# Sheet1.net
KiCad netlist of a schematic drawn in Altium Designer
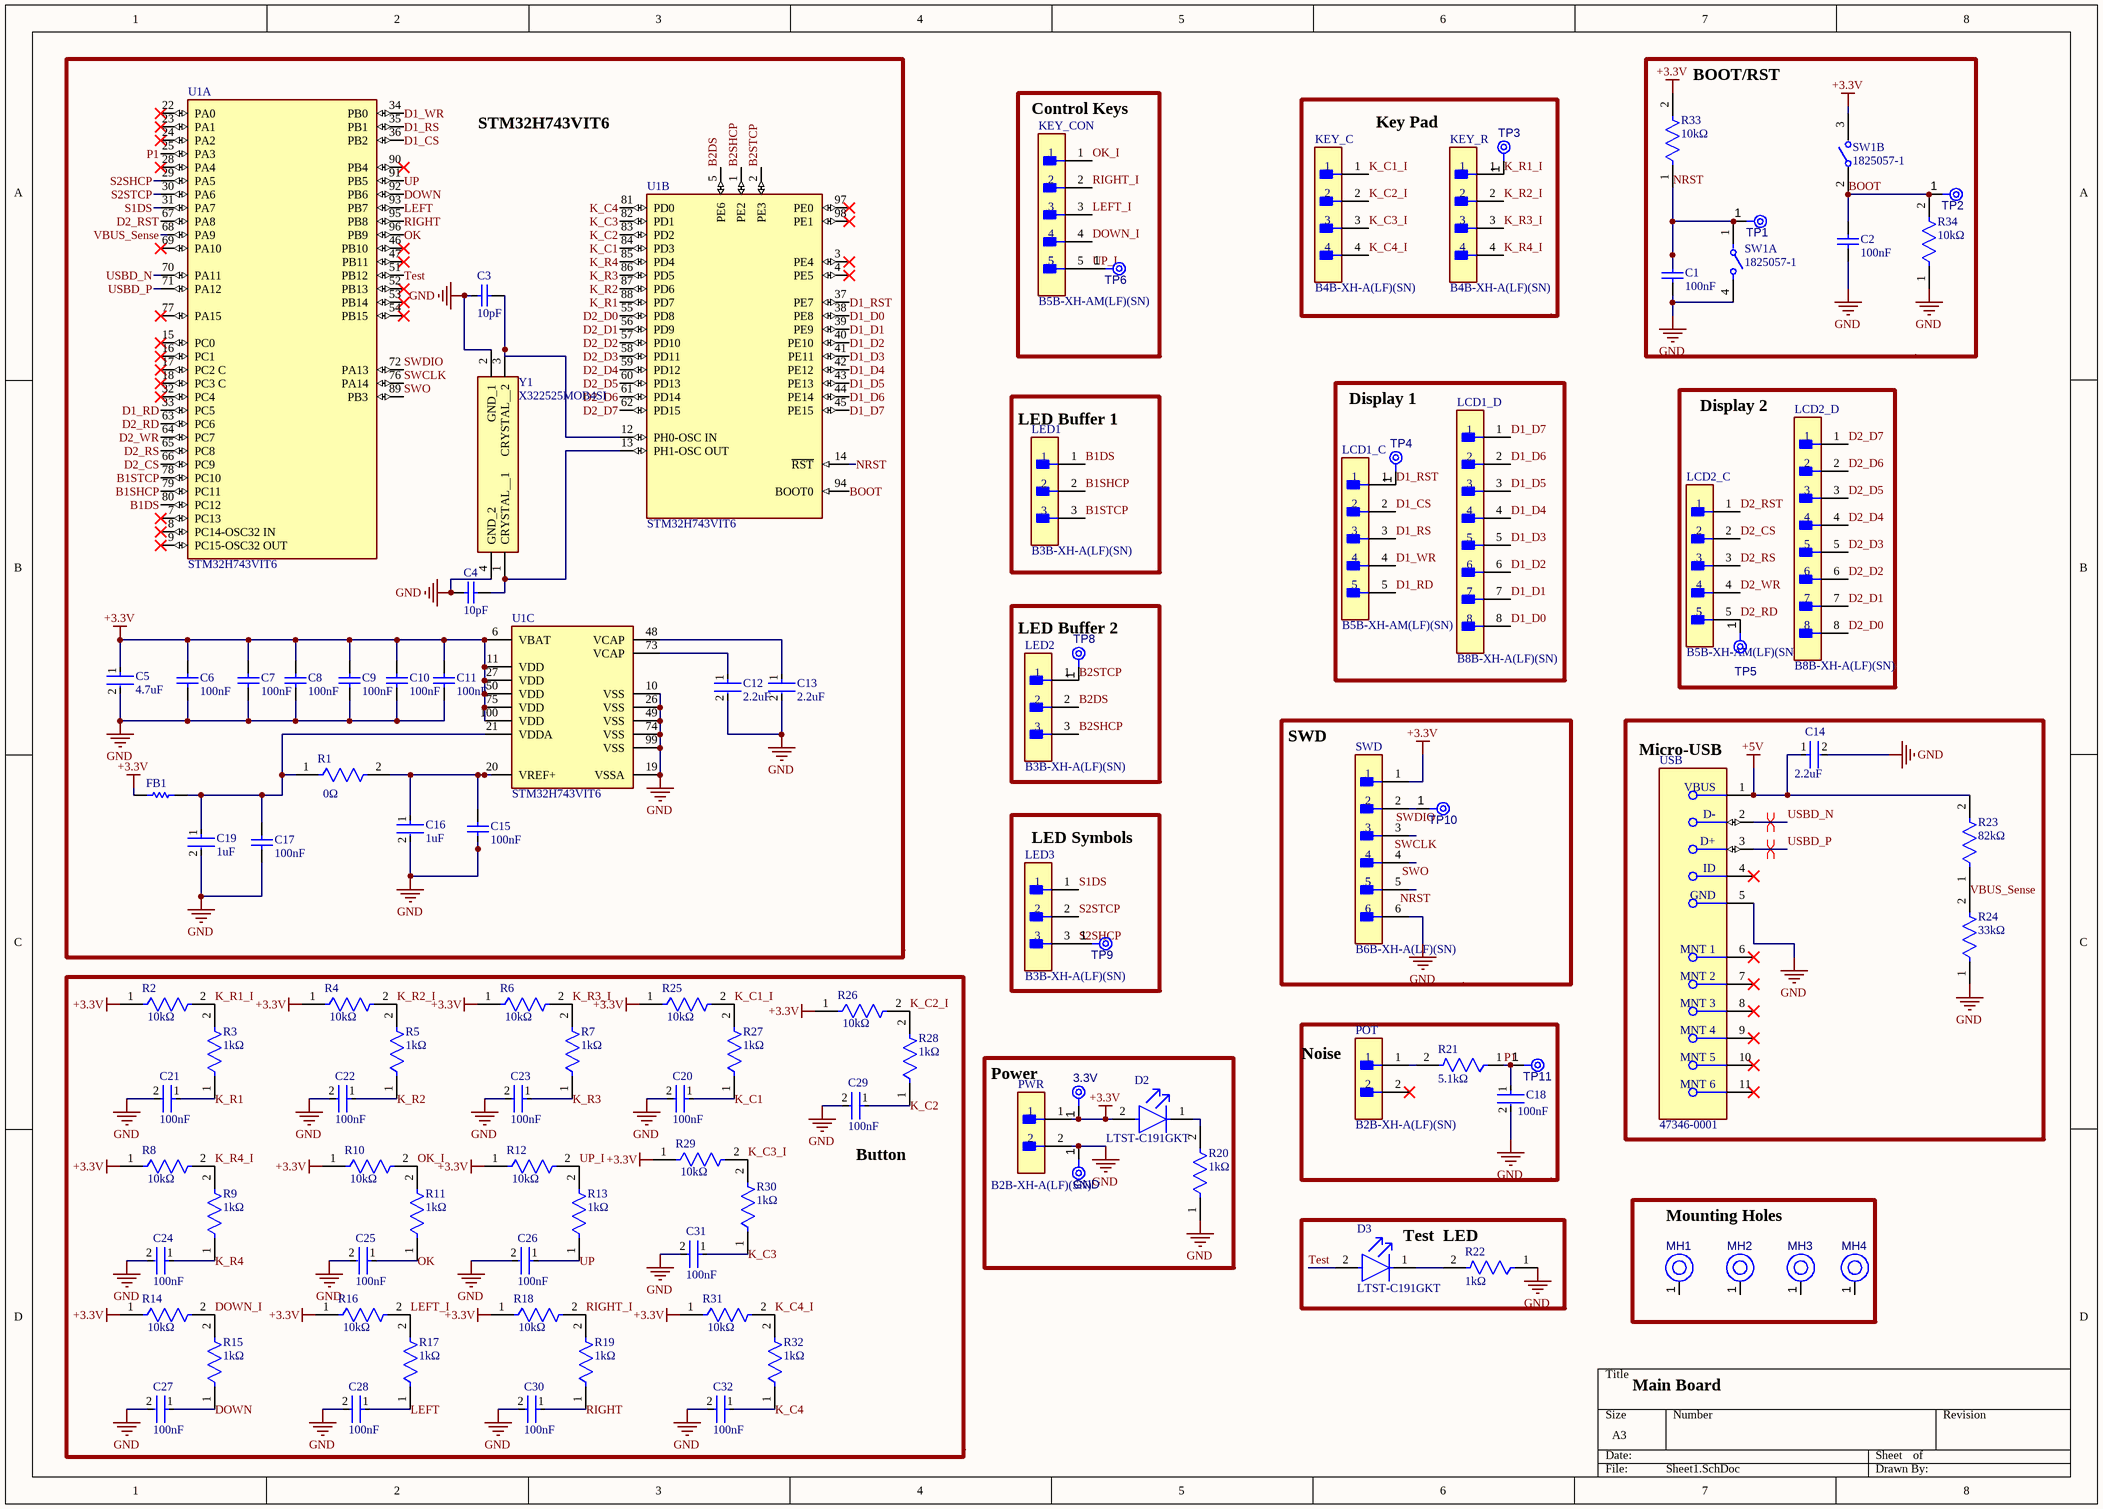
[diagram p0: Sheet1.SchDoc]

(export (version "E")
  (design (tool "Eeschema 10.0.6"))
  (components
    (comp (ref "3.3V")
      (value "TPAD6R")
      (footprint "TP06R")
      (description "0.6mm round")
      (libsource (lib "ravindu tennakoon") (part "CMP-001-0001-4"))
    )
    (comp (ref "C1")
      (value "100nF")
      (footprint "CAPC1050X55X23ML05T13")
      (description "Chip Capacitor, 100 nF, +/- 10%, 16 V, -55 to 125 degC, 0402 (1005 Metric), RoHS, Tape and Reel")
      (fields (field (name "MANUFACTURER") "Samsung Electro-Mechanics"))
      (libsource (lib "Altium Content Vault") (part "CAP-NP-2"))
    )
    (comp (ref "C2")
      (value "100nF")
      (footprint "CAPC1050X55X23ML05T13")
      (description "Chip Capacitor, 100 nF, +/- 10%, 16 V, -55 to 125 degC, 0402 (1005 Metric), RoHS, Tape and Reel")
      (fields (field (name "MANUFACTURER") "Samsung Electro-Mechanics"))
      (libsource (lib "Altium Content Vault") (part "CAP-NP-2"))
    )
    (comp (ref "C3")
      (value "10pF")
      (footprint "CAPC1050X55X23ML05T13")
      (fields (field (name "MANUFACTURER") "Samsung Electro-Mechanics"))
      (libsource (lib "Altium Content Vault") (part "CAP-NP-2"))
    )
    (comp (ref "C4")
      (value "10pF")
      (footprint "CAPC1050X55X23ML05T13")
      (fields (field (name "MANUFACTURER") "Samsung Electro-Mechanics"))
      (libsource (lib "Altium Content Vault") (part "CAP-NP-2"))
    )
    (comp (ref "C5")
      (value "4.7uF")
      (footprint "FP-CC0603-DA-MFG")
      (description "CC0603KRX5R8BB475 CAP CER 4.7UF 25V X5R 0603")
      (fields
        (field (name "MANUFACTURER") "YAGEO")
        (field (name "MANUFACTURER PART NUMBER") "CC0603KRX5R8BB475")
      )
      (libsource (lib "Altium Content Vault") (part "11868f565c42a9108669ba33697ecf6"))
    )
    (comp (ref "C6")
      (value "100nF")
      (footprint "CAPC1050X55X23ML05T13")
      (fields (field (name "MANUFACTURER") "Samsung Electro-Mechanics"))
      (libsource (lib "Altium Content Vault") (part "CAP-NP-2"))
    )
    (comp (ref "C7")
      (value "100nF")
      (footprint "CAPC1050X55X23ML05T13")
      (description "Chip Capacitor, 100 nF, +/- 10%, 16 V, -55 to 125 degC, 0402 (1005 Metric), RoHS, Tape and Reel")
      (fields (field (name "MANUFACTURER") "Samsung Electro-Mechanics"))
      (libsource (lib "Altium Content Vault") (part "CAP-NP-2"))
    )
    (comp (ref "C8")
      (value "100nF")
      (footprint "CAPC1050X55X23ML05T13")
      (description "Chip Capacitor, 100 nF, +/- 10%, 16 V, -55 to 125 degC, 0402 (1005 Metric), RoHS, Tape and Reel")
      (fields (field (name "MANUFACTURER") "Samsung Electro-Mechanics"))
      (libsource (lib "Altium Content Vault") (part "CAP-NP-2"))
    )
    (comp (ref "C9")
      (value "100nF")
      (footprint "CAPC1050X55X23ML05T13")
      (description "Chip Capacitor, 100 nF, +/- 10%, 16 V, -55 to 125 degC, 0402 (1005 Metric), RoHS, Tape and Reel")
      (fields (field (name "MANUFACTURER") "Samsung Electro-Mechanics"))
      (libsource (lib "Altium Content Vault") (part "CAP-NP-2"))
    )
    (comp (ref "C10")
      (value "100nF")
      (footprint "CAPC1050X55X23ML05T13")
      (description "Chip Capacitor, 100 nF, +/- 10%, 16 V, -55 to 125 degC, 0402 (1005 Metric), RoHS, Tape and Reel")
      (fields (field (name "MANUFACTURER") "Samsung Electro-Mechanics"))
      (libsource (lib "Altium Content Vault") (part "CAP-NP-2"))
    )
    (comp (ref "C11")
      (value "100nF")
      (footprint "CAPC1050X55X23ML05T13")
      (description "Chip Capacitor, 100 nF, +/- 10%, 16 V, -55 to 125 degC, 0402 (1005 Metric), RoHS, Tape and Reel")
      (fields (field (name "MANUFACTURER") "Samsung Electro-Mechanics"))
      (libsource (lib "Altium Content Vault") (part "CAP-NP-2"))
    )
    (comp (ref "C12")
      (value "2.2uF")
      (footprint "FP-CL10-IPC_A")
      (description "CL10A225KO8NNNC Cap Ceramic 2.2uF 16V X5R ±10% Pad SMD 0603 +85°C T/R")
      (fields (field (name "TOLERANCE") "10%") (field (name "VOLTAGE") "16V"))
      (libsource (lib "Altium Content Vault") (part "b4654b650e69147ec39a6b967a45e02"))
    )
    (comp (ref "C13")
      (value "2.2uF")
      (footprint "FP-CL10-IPC_A")
      (description "CL10A225KO8NNNC Cap Ceramic 2.2uF 16V X5R ±10% Pad SMD 0603 +85°C T/R")
      (fields (field (name "TOLERANCE") "10%") (field (name "VOLTAGE") "16V"))
      (libsource (lib "Altium Content Vault") (part "b4654b650e69147ec39a6b967a45e02"))
    )
    (comp (ref "C14")
      (value "2.2uF")
      (footprint "FP-C1210C225K1RACAUTO-MFG")
      (description "C1210C225K1RACAUTOCAP CER 2.2UF 100V X7R 1210")
      (fields (field (name "TOLERANCE") "10%"))
      (libsource (lib "Altium Content Vault") (part "b4654b650e69147ec39a6b967a45e02"))
    )
    (comp (ref "C15")
      (value "100nF")
      (footprint "CAPC1050X55X23ML05T13")
      (description "Chip Capacitor, 100 nF, +/- 10%, 16 V, -55 to 125 degC, 0402 (1005 Metric), RoHS, Tape and Reel")
      (fields (field (name "MANUFACTURER") "Samsung Electro-Mechanics"))
      (libsource (lib "Altium Content Vault") (part "CAP-NP-2"))
    )
    (comp (ref "C16")
      (value "1uF")
      (footprint "FP-CL10-IPC_A")
      (description "CL10A105KO8NNNC Cap Ceramic 1uF 16V X5R ±10% Pad SMD 0603 +85°C T/R")
      (fields (field (name "TOLERANCE") "10%") (field (name "VOLTAGE") "16V"))
      (libsource (lib "Altium Content Vault") (part "b4654b650e69147ec39a6b967a45e02"))
    )
    (comp (ref "C17")
      (value "100nF")
      (footprint "CAPC1050X55X23ML05T13")
      (description "Chip Capacitor, 100 nF, +/- 10%, 16 V, -55 to 125 degC, 0402 (1005 Metric), RoHS, Tape and Reel")
      (fields (field (name "MANUFACTURER") "Samsung Electro-Mechanics"))
      (libsource (lib "Altium Content Vault") (part "CAP-NP-2"))
    )
    (comp (ref "C18")
      (value "100nF")
      (footprint "FP-CL21-IPC_A")
      (description "CL21B104KCFWPNE CL21 Series 0805 100nF 100V ±10% Tolerance X7R Multilayer Ceramic Chip Capacitor")
      (fields (field (name "TOLERANCE") "10%"))
      (libsource (lib "Altium Content Vault") (part "b4654b650e69147ec39a6b967a45e02"))
    )
    (comp (ref "C19")
      (value "1uF")
      (footprint "FP-CL10-IPC_A")
      (description "CL10A105KO8NNNC Cap Ceramic 1uF 16V X5R ±10% Pad SMD 0603 +85°C T/R")
      (fields (field (name "TOLERANCE") "10%") (field (name "VOLTAGE") "16V"))
      (libsource (lib "Altium Content Vault") (part "b4654b650e69147ec39a6b967a45e02"))
    )
    (comp (ref "C20")
      (value "100nF")
      (footprint "FP-CL21-IPC_A")
      (description "CL21B104KCFWPNE CL21 Series 0805 100nF 100V ±10% Tolerance X7R Multilayer Ceramic Chip Capacitor")
      (fields (field (name "TOLERANCE") "10%"))
      (libsource (lib "Altium Content Vault") (part "b4654b650e69147ec39a6b967a45e02"))
    )
    (comp (ref "C21")
      (value "100nF")
      (footprint "FP-CL21-IPC_A")
      (description "CL21B104KCFWPNE CL21 Series 0805 100nF 100V ±10% Tolerance X7R Multilayer Ceramic Chip Capacitor")
      (fields (field (name "TOLERANCE") "10%"))
      (libsource (lib "Altium Content Vault") (part "b4654b650e69147ec39a6b967a45e02"))
    )
    (comp (ref "C22")
      (value "100nF")
      (footprint "FP-CL21-IPC_A")
      (description "CL21B104KCFWPNE CL21 Series 0805 100nF 100V ±10% Tolerance X7R Multilayer Ceramic Chip Capacitor")
      (fields (field (name "TOLERANCE") "10%"))
      (libsource (lib "Altium Content Vault") (part "b4654b650e69147ec39a6b967a45e02"))
    )
    (comp (ref "C23")
      (value "100nF")
      (footprint "FP-CL21-IPC_A")
      (description "CL21B104KCFWPNE CL21 Series 0805 100nF 100V ±10% Tolerance X7R Multilayer Ceramic Chip Capacitor")
      (fields (field (name "TOLERANCE") "10%"))
      (libsource (lib "Altium Content Vault") (part "b4654b650e69147ec39a6b967a45e02"))
    )
    (comp (ref "C24")
      (value "100nF")
      (footprint "FP-CL21-IPC_A")
      (description "CL21B104KCFWPNE CL21 Series 0805 100nF 100V ±10% Tolerance X7R Multilayer Ceramic Chip Capacitor")
      (fields (field (name "TOLERANCE") "10%"))
      (libsource (lib "Altium Content Vault") (part "b4654b650e69147ec39a6b967a45e02"))
    )
    (comp (ref "C25")
      (value "100nF")
      (footprint "FP-CL21-IPC_A")
      (description "CL21B104KCFWPNE CL21 Series 0805 100nF 100V ±10% Tolerance X7R Multilayer Ceramic Chip Capacitor")
      (fields (field (name "TOLERANCE") "10%"))
      (libsource (lib "Altium Content Vault") (part "b4654b650e69147ec39a6b967a45e02"))
    )
    (comp (ref "C26")
      (value "100nF")
      (footprint "FP-CL21-IPC_A")
      (description "CL21B104KCFWPNE CL21 Series 0805 100nF 100V ±10% Tolerance X7R Multilayer Ceramic Chip Capacitor")
      (fields (field (name "TOLERANCE") "10%"))
      (libsource (lib "Altium Content Vault") (part "b4654b650e69147ec39a6b967a45e02"))
    )
    (comp (ref "C27")
      (value "100nF")
      (footprint "FP-CL21-IPC_A")
      (description "CL21B104KCFWPNE CL21 Series 0805 100nF 100V ±10% Tolerance X7R Multilayer Ceramic Chip Capacitor")
      (fields (field (name "TOLERANCE") "10%"))
      (libsource (lib "Altium Content Vault") (part "b4654b650e69147ec39a6b967a45e02"))
    )
    (comp (ref "C28")
      (value "100nF")
      (footprint "FP-CL21-IPC_A")
      (description "CL21B104KCFWPNE CL21 Series 0805 100nF 100V ±10% Tolerance X7R Multilayer Ceramic Chip Capacitor")
      (fields (field (name "TOLERANCE") "10%"))
      (libsource (lib "Altium Content Vault") (part "b4654b650e69147ec39a6b967a45e02"))
    )
    (comp (ref "C29")
      (value "100nF")
      (footprint "FP-CL21-IPC_A")
      (description "CL21B104KCFWPNE CL21 Series 0805 100nF 100V ±10% Tolerance X7R Multilayer Ceramic Chip Capacitor")
      (fields (field (name "TOLERANCE") "10%"))
      (libsource (lib "Altium Content Vault") (part "b4654b650e69147ec39a6b967a45e02"))
    )
    (comp (ref "C30")
      (value "100nF")
      (footprint "FP-CL21-IPC_A")
      (description "CL21B104KCFWPNE CL21 Series 0805 100nF 100V ±10% Tolerance X7R Multilayer Ceramic Chip Capacitor")
      (fields (field (name "TOLERANCE") "10%"))
      (libsource (lib "Altium Content Vault") (part "b4654b650e69147ec39a6b967a45e02"))
    )
    (comp (ref "C31")
      (value "100nF")
      (footprint "FP-CL21-IPC_A")
      (description "CL21B104KCFWPNE CL21 Series 0805 100nF 100V ±10% Tolerance X7R Multilayer Ceramic Chip Capacitor")
      (fields (field (name "TOLERANCE") "10%"))
      (libsource (lib "Altium Content Vault") (part "b4654b650e69147ec39a6b967a45e02"))
    )
    (comp (ref "C32")
      (value "100nF")
      (footprint "FP-CL21-IPC_A")
      (description "CL21B104KCFWPNE CL21 Series 0805 100nF 100V ±10% Tolerance X7R Multilayer Ceramic Chip Capacitor")
      (fields (field (name "TOLERANCE") "10%"))
      (libsource (lib "Altium Content Vault") (part "b4654b650e69147ec39a6b967a45e02"))
    )
    (comp (ref "D2")
      (value "LTST-C191GKT")
      (footprint "FP-LTST-C191GKT-MFG")
      (description "LED GREEN CLEAR CHIP SMD")
      (libsource (lib "Altium Content Vault") (part "8706943c75ba83719d021d2fdc84c58"))
    )
    (comp (ref "D3")
      (value "LTST-C191GKT")
      (footprint "FP-LTST-C191GKT-MFG")
      (description "LED GREEN CLEAR CHIP SMD")
      (libsource (lib "Altium Content Vault") (part "8706943c75ba83719d021d2fdc84c58"))
    )
    (comp (ref "FB1")
      (value "~")
      (footprint "RESC1609X55X30LL10T20")
      (description "1206W4F0000T5E")
      (fields (field (name "PART NUMBER") "TNPU0603100RBZEN00") (field (name "MANUFACTURER") "Vishay Dale"))
      (libsource (lib "Altium Content Vault") (part "RES"))
    )
    (comp (ref "GND")
      (value "TPAD6R")
      (footprint "TP06R")
      (description "0.6mm round")
      (libsource (lib "ravindu tennakoon") (part "CMP-001-0001-4"))
    )
    (comp (ref "KEY_C")
      (value "B4B-XH-A(LF)(SN)")
      (footprint "FP-B4B-XH-A_LF_SN-MFG")
      (description "CONN HEADER VERT 4POS 2.5MM")
      (libsource (lib "Altium Content Vault") (part "299a8cea1bdcbc3624fe62c390fa72c"))
    )
    (comp (ref "KEY_CON")
      (value "B5B-XH-AM(LF)(SN)")
      (footprint "FP-B5B-XH-AM_LF_SN-MFG")
      (description "CONN HEADER VERT 5POS 2.5MM")
      (libsource (lib "Altium Content Vault") (part "bf93c07fd2649a848d0ec8585582aab"))
    )
    (comp (ref "KEY_R")
      (value "B4B-XH-A(LF)(SN)")
      (footprint "FP-B4B-XH-A_LF_SN-MFG")
      (description "CONN HEADER VERT 4POS 2.5MM")
      (libsource (lib "Altium Content Vault") (part "299a8cea1bdcbc3624fe62c390fa72c"))
    )
    (comp (ref "LCD1_C")
      (value "B5B-XH-AM(LF)(SN)")
      (footprint "FP-B5B-XH-AM_LF_SN-MFG")
      (description "CONN HEADER VERT 5POS 2.5MM")
      (libsource (lib "Altium Content Vault") (part "bf93c07fd2649a848d0ec8585582aab"))
    )
    (comp (ref "LCD1_D")
      (value "B8B-XH-A(LF)(SN)")
      (footprint "FP-B8B-XH-A_LF_SN-MFG")
      (description "CONN HEADER VERT 8POS 2.5MM")
      (libsource (lib "Altium Content Vault") (part "99ec2b232beb5d2356d4d77f6a047f0"))
    )
    (comp (ref "LCD2_C")
      (value "B5B-XH-AM(LF)(SN)")
      (footprint "FP-B5B-XH-AM_LF_SN-MFG")
      (description "CONN HEADER VERT 5POS 2.5MM")
      (libsource (lib "Altium Content Vault") (part "bf93c07fd2649a848d0ec8585582aab"))
    )
    (comp (ref "LCD2_D")
      (value "B8B-XH-A(LF)(SN)")
      (footprint "FP-B8B-XH-A_LF_SN-MFG")
      (description "CONN HEADER VERT 8POS 2.5MM")
      (libsource (lib "Altium Content Vault") (part "99ec2b232beb5d2356d4d77f6a047f0"))
    )
    (comp (ref "LED1")
      (value "B3B-XH-A(LF)(SN)")
      (footprint "FP-B3B-XH-A_LF_SN-MFG")
      (description "CONN HEADER VERT 3POS 2.5MM")
      (libsource (lib "Altium Content Vault") (part "0d3f023dd272f625e17a2be33dea85f"))
    )
    (comp (ref "LED2")
      (value "B3B-XH-A(LF)(SN)")
      (footprint "FP-B3B-XH-A_LF_SN-MFG")
      (description "CONN HEADER VERT 3POS 2.5MM")
      (libsource (lib "Altium Content Vault") (part "0d3f023dd272f625e17a2be33dea85f"))
    )
    (comp (ref "LED3")
      (value "B3B-XH-A(LF)(SN)")
      (footprint "FP-B3B-XH-A_LF_SN-MFG")
      (description "CONN HEADER VERT 3POS 2.5MM")
      (libsource (lib "Altium Content Vault") (part "0d3f023dd272f625e17a2be33dea85f"))
    )
    (comp (ref "MH1")
      (value "PTH")
      (footprint "Copy of PTH-M2D5X5")
      (description "4mm, 3.2mm")
      (libsource (lib "ravindu tennakoon") (part "Copy of CMP-00028-00000-1"))
    )
    (comp (ref "MH2")
      (value "PTH")
      (footprint "Copy of PTH-M2D5X5")
      (description "4mm, 3.2mm")
      (libsource (lib "ravindu tennakoon") (part "Copy of CMP-00028-00000-1"))
    )
    (comp (ref "MH3")
      (value "PTH")
      (footprint "Copy of PTH-M2D5X5")
      (description "4mm, 3.2mm")
      (libsource (lib "ravindu tennakoon") (part "Copy of CMP-00028-00000-1"))
    )
    (comp (ref "MH4")
      (value "PTH")
      (footprint "Copy of PTH-M2D5X5")
      (description "4mm, 3.2mm")
      (libsource (lib "ravindu tennakoon") (part "Copy of CMP-00028-00000-1"))
    )
    (comp (ref "POT")
      (value "B2B-XH-A(LF)(SN)")
      (footprint "FP-B2B-XH-A_LF_SN-MFG")
      (description "CONN HEADER VERT 2POS 2.5MM")
      (libsource (lib "Altium Content Vault") (part "3bc925449376181038e59eaffc5286c"))
    )
    (comp (ref "PWR")
      (value "B2B-XH-A(LF)(SN)")
      (footprint "FP-B2B-XH-A_LF_SN-MFG")
      (description "CONN HEADER VERT 2POS 2.5MM")
      (libsource (lib "Altium Content Vault") (part "3bc925449376181038e59eaffc5286c"))
    )
    (comp (ref "R1")
      (value "0Ω")
      (footprint "FP-AC1206-MFG")
      (description "1206W4F0000T5E")
      (fields
        (field (name "MANUFACTURER PART NUMBER") "AC1206FR-07267RL")
        (field (name "OCTOPART") "https://octopart.com/ac1206fr-07267rl-yageo-71368055")
      )
      (libsource (lib "Altium Content Vault") (part "1029c3af85768c4190bb7ad29bc67b5"))
    )
    (comp (ref "R2")
      (value "10kΩ")
      (footprint "FP-SR0805-MFG")
      (description "RES SMD 0805 1/2W 1% 10K OHM")
      (fields (field (name "MANUFACTURER PART NUMBER") "SR0805FR-4710KL") (field (name "TOLERANCE") "0.01"))
      (libsource (lib "Altium Content Vault") (part "1029c3af85768c4190bb7ad29bc67b5"))
    )
    (comp (ref "R3")
      (value "1kΩ")
      (footprint "FP-SR0805-MFG")
      (description "RMC08051K5%N")
      (fields (field (name "MANUFACTURER PART NUMBER") "SR0805FR-4710KL") (field (name "TOLERANCE") "0.01"))
      (libsource (lib "Altium Content Vault") (part "1029c3af85768c4190bb7ad29bc67b5"))
    )
    (comp (ref "R4")
      (value "10kΩ")
      (footprint "FP-SR0805-MFG")
      (description "RES SMD 0805 1/2W 1% 10K OHM")
      (fields (field (name "MANUFACTURER PART NUMBER") "SR0805FR-4710KL") (field (name "TOLERANCE") "0.01"))
      (libsource (lib "Altium Content Vault") (part "1029c3af85768c4190bb7ad29bc67b5"))
    )
    (comp (ref "R5")
      (value "1kΩ")
      (footprint "FP-SR0805-MFG")
      (description "RMC08051K5%N")
      (fields (field (name "MANUFACTURER PART NUMBER") "SR0805FR-4710KL") (field (name "TOLERANCE") "0.01"))
      (libsource (lib "Altium Content Vault") (part "1029c3af85768c4190bb7ad29bc67b5"))
    )
    (comp (ref "R6")
      (value "10kΩ")
      (footprint "FP-SR0805-MFG")
      (description "RES SMD 0805 1/2W 1% 10K OHM")
      (fields (field (name "MANUFACTURER PART NUMBER") "SR0805FR-4710KL") (field (name "TOLERANCE") "0.01"))
      (libsource (lib "Altium Content Vault") (part "1029c3af85768c4190bb7ad29bc67b5"))
    )
    (comp (ref "R7")
      (value "1kΩ")
      (footprint "FP-SR0805-MFG")
      (description "RMC08051K5%N")
      (fields (field (name "MANUFACTURER PART NUMBER") "SR0805FR-4710KL") (field (name "TOLERANCE") "0.01"))
      (libsource (lib "Altium Content Vault") (part "1029c3af85768c4190bb7ad29bc67b5"))
    )
    (comp (ref "R8")
      (value "10kΩ")
      (footprint "FP-SR0805-MFG")
      (description "RES SMD 0805 1/2W 1% 10K OHM")
      (fields (field (name "MANUFACTURER PART NUMBER") "SR0805FR-4710KL") (field (name "TOLERANCE") "0.01"))
      (libsource (lib "Altium Content Vault") (part "1029c3af85768c4190bb7ad29bc67b5"))
    )
    (comp (ref "R9")
      (value "1kΩ")
      (footprint "FP-SR0805-MFG")
      (description "RMC08051K5%N")
      (fields (field (name "MANUFACTURER PART NUMBER") "SR0805FR-4710KL") (field (name "TOLERANCE") "0.01"))
      (libsource (lib "Altium Content Vault") (part "1029c3af85768c4190bb7ad29bc67b5"))
    )
    (comp (ref "R10")
      (value "10kΩ")
      (footprint "FP-SR0805-MFG")
      (description "RES SMD 0805 1/2W 1% 10K OHM")
      (fields (field (name "MANUFACTURER PART NUMBER") "SR0805FR-4710KL") (field (name "TOLERANCE") "0.01"))
      (libsource (lib "Altium Content Vault") (part "1029c3af85768c4190bb7ad29bc67b5"))
    )
    (comp (ref "R11")
      (value "1kΩ")
      (footprint "FP-SR0805-MFG")
      (description "RMC08051K5%N")
      (fields (field (name "MANUFACTURER PART NUMBER") "SR0805FR-4710KL") (field (name "TOLERANCE") "0.01"))
      (libsource (lib "Altium Content Vault") (part "1029c3af85768c4190bb7ad29bc67b5"))
    )
    (comp (ref "R12")
      (value "10kΩ")
      (footprint "FP-SR0805-MFG")
      (description "RES SMD 0805 1/2W 1% 10K OHM")
      (fields (field (name "MANUFACTURER PART NUMBER") "SR0805FR-4710KL") (field (name "TOLERANCE") "0.01"))
      (libsource (lib "Altium Content Vault") (part "1029c3af85768c4190bb7ad29bc67b5"))
    )
    (comp (ref "R13")
      (value "1kΩ")
      (footprint "FP-SR0805-MFG")
      (description "RMC08051K5%N")
      (fields (field (name "MANUFACTURER PART NUMBER") "SR0805FR-4710KL") (field (name "TOLERANCE") "0.01"))
      (libsource (lib "Altium Content Vault") (part "1029c3af85768c4190bb7ad29bc67b5"))
    )
    (comp (ref "R14")
      (value "10kΩ")
      (footprint "FP-SR0805-MFG")
      (description "RES SMD 0805 1/2W 1% 10K OHM")
      (fields (field (name "MANUFACTURER PART NUMBER") "SR0805FR-4710KL") (field (name "TOLERANCE") "0.01"))
      (libsource (lib "Altium Content Vault") (part "1029c3af85768c4190bb7ad29bc67b5"))
    )
    (comp (ref "R15")
      (value "1kΩ")
      (footprint "FP-SR0805-MFG")
      (description "RMC08051K5%N")
      (fields (field (name "MANUFACTURER PART NUMBER") "SR0805FR-4710KL") (field (name "TOLERANCE") "0.01"))
      (libsource (lib "Altium Content Vault") (part "1029c3af85768c4190bb7ad29bc67b5"))
    )
    (comp (ref "R16")
      (value "10kΩ")
      (footprint "FP-SR0805-MFG")
      (description "RES SMD 0805 1/2W 1% 10K OHM")
      (fields (field (name "MANUFACTURER PART NUMBER") "SR0805FR-4710KL") (field (name "TOLERANCE") "0.01"))
      (libsource (lib "Altium Content Vault") (part "1029c3af85768c4190bb7ad29bc67b5"))
    )
    (comp (ref "R17")
      (value "1kΩ")
      (footprint "FP-SR0805-MFG")
      (description "RMC08051K5%N")
      (fields (field (name "MANUFACTURER PART NUMBER") "SR0805FR-4710KL") (field (name "TOLERANCE") "0.01"))
      (libsource (lib "Altium Content Vault") (part "1029c3af85768c4190bb7ad29bc67b5"))
    )
    (comp (ref "R18")
      (value "10kΩ")
      (footprint "FP-SR0805-MFG")
      (description "RES SMD 0805 1/2W 1% 10K OHM")
      (fields (field (name "MANUFACTURER PART NUMBER") "SR0805FR-4710KL") (field (name "TOLERANCE") "0.01"))
      (libsource (lib "Altium Content Vault") (part "1029c3af85768c4190bb7ad29bc67b5"))
    )
    (comp (ref "R19")
      (value "1kΩ")
      (footprint "FP-SR0805-MFG")
      (description "RMC08051K5%N")
      (fields (field (name "MANUFACTURER PART NUMBER") "SR0805FR-4710KL") (field (name "TOLERANCE") "0.01"))
      (libsource (lib "Altium Content Vault") (part "1029c3af85768c4190bb7ad29bc67b5"))
    )
    (comp (ref "R20")
      (value "1kΩ")
      (footprint "FP-SR0805-MFG")
      (description "RMC08051K5%N")
      (fields (field (name "MANUFACTURER PART NUMBER") "SR0805FR-4710KL") (field (name "TOLERANCE") "0.01"))
      (libsource (lib "Altium Content Vault") (part "1029c3af85768c4190bb7ad29bc67b5"))
    )
    (comp (ref "R21")
      (value "5.1kΩ")
      (footprint "FP-SR0805-MFG")
      (description "0805W8F1501T5E")
      (fields (field (name "MANUFACTURER PART NUMBER") "SR0805FR-4710KL") (field (name "TOLERANCE") "0.01"))
      (libsource (lib "Altium Content Vault") (part "1029c3af85768c4190bb7ad29bc67b5"))
    )
    (comp (ref "R22")
      (value "1kΩ")
      (footprint "FP-SR0805-MFG")
      (description "RMC08051K5%N")
      (fields (field (name "MANUFACTURER PART NUMBER") "SR0805FR-4710KL") (field (name "TOLERANCE") "0.01"))
      (libsource (lib "Altium Content Vault") (part "1029c3af85768c4190bb7ad29bc67b5"))
    )
    (comp (ref "R23")
      (value "82kΩ")
      (footprint "FP-SR0805-MFG")
      (description "0805W8F8202T5E")
      (fields (field (name "MANUFACTURER PART NUMBER") "SR0805FR-4710KL") (field (name "TOLERANCE") "0.01"))
      (libsource (lib "Altium Content Vault") (part "1029c3af85768c4190bb7ad29bc67b5"))
    )
    (comp (ref "R24")
      (value "33kΩ")
      (footprint "FP-SR0805-MFG")
      (description "0805W8F3302T5E")
      (fields (field (name "MANUFACTURER PART NUMBER") "SR0805FR-4710KL") (field (name "TOLERANCE") "0.01"))
      (libsource (lib "Altium Content Vault") (part "1029c3af85768c4190bb7ad29bc67b5"))
    )
    (comp (ref "R25")
      (value "10kΩ")
      (footprint "FP-SR0805-MFG")
      (description "RES SMD 0805 1/2W 1% 10K OHM")
      (fields (field (name "MANUFACTURER PART NUMBER") "SR0805FR-4710KL") (field (name "TOLERANCE") "0.01"))
      (libsource (lib "Altium Content Vault") (part "1029c3af85768c4190bb7ad29bc67b5"))
    )
    (comp (ref "R26")
      (value "10kΩ")
      (footprint "FP-SR0805-MFG")
      (description "RES SMD 0805 1/2W 1% 10K OHM")
      (fields (field (name "MANUFACTURER PART NUMBER") "SR0805FR-4710KL") (field (name "TOLERANCE") "0.01"))
      (libsource (lib "Altium Content Vault") (part "1029c3af85768c4190bb7ad29bc67b5"))
    )
    (comp (ref "R27")
      (value "1kΩ")
      (footprint "FP-SR0805-MFG")
      (description "RMC08051K5%N")
      (fields (field (name "MANUFACTURER PART NUMBER") "SR0805FR-4710KL") (field (name "TOLERANCE") "0.01"))
      (libsource (lib "Altium Content Vault") (part "1029c3af85768c4190bb7ad29bc67b5"))
    )
    (comp (ref "R28")
      (value "1kΩ")
      (footprint "FP-SR0805-MFG")
      (description "RMC08051K5%N")
      (fields (field (name "MANUFACTURER PART NUMBER") "SR0805FR-4710KL") (field (name "TOLERANCE") "0.01"))
      (libsource (lib "Altium Content Vault") (part "1029c3af85768c4190bb7ad29bc67b5"))
    )
    (comp (ref "R29")
      (value "10kΩ")
      (footprint "FP-SR0805-MFG")
      (description "RES SMD 0805 1/2W 1% 10K OHM")
      (fields (field (name "MANUFACTURER PART NUMBER") "SR0805FR-4710KL") (field (name "TOLERANCE") "0.01"))
      (libsource (lib "Altium Content Vault") (part "1029c3af85768c4190bb7ad29bc67b5"))
    )
    (comp (ref "R30")
      (value "1kΩ")
      (footprint "FP-SR0805-MFG")
      (description "RMC08051K5%N")
      (fields (field (name "MANUFACTURER PART NUMBER") "SR0805FR-4710KL") (field (name "TOLERANCE") "0.01"))
      (libsource (lib "Altium Content Vault") (part "1029c3af85768c4190bb7ad29bc67b5"))
    )
    (comp (ref "R31")
      (value "10kΩ")
      (footprint "FP-SR0805-MFG")
      (description "RES SMD 0805 1/2W 1% 10K OHM")
      (fields (field (name "MANUFACTURER PART NUMBER") "SR0805FR-4710KL") (field (name "TOLERANCE") "0.01"))
      (libsource (lib "Altium Content Vault") (part "1029c3af85768c4190bb7ad29bc67b5"))
    )
    (comp (ref "R32")
      (value "1kΩ")
      (footprint "FP-SR0805-MFG")
      (description "RMC08051K5%N")
      (fields (field (name "MANUFACTURER PART NUMBER") "SR0805FR-4710KL") (field (name "TOLERANCE") "0.01"))
      (libsource (lib "Altium Content Vault") (part "1029c3af85768c4190bb7ad29bc67b5"))
    )
    (comp (ref "R33")
      (value "10kΩ")
      (footprint "FP-SR0805-MFG")
      (description "RES SMD 0805 1/2W 1% 10K OHM")
      (fields (field (name "MANUFACTURER PART NUMBER") "SR0805FR-4710KL") (field (name "TOLERANCE") "0.01"))
      (libsource (lib "Altium Content Vault") (part "1029c3af85768c4190bb7ad29bc67b5"))
    )
    (comp (ref "R34")
      (value "10kΩ")
      (footprint "FP-SR0805-MFG")
      (description "RES SMD 0805 1/2W 1% 10K OHM")
      (fields (field (name "MANUFACTURER PART NUMBER") "SR0805FR-4710KL") (field (name "TOLERANCE") "0.01"))
      (libsource (lib "Altium Content Vault") (part "1029c3af85768c4190bb7ad29bc67b5"))
    )
    (comp (ref "SW1")
      (value "1825057-1")
      (footprint "FP-1825057-1-MFG")
      (description "SWITCH SLIDE DIP SPST 100MA 24V")
      (fields
        (field (name "OCTOPART") "https://octopart.com/1825057-1-te+connectivity-46507313")
        (field (name "MANUFACTURER") "TE Connectivity")
      )
      (libsource (lib "Altium Content Vault") (part "305b8df74c9585226458c49fb7f7021"))
    )
    (comp (ref "SWD")
      (value "B6B-XH-A(LF)(SN)")
      (footprint "FP-B6B-XH-A_LF_SN-MFG")
      (description "CONN HEADER VERT 6POS 2.5MM")
      (libsource (lib "Altium Content Vault") (part "f2cb566baf1c37ab5a3b8e90bbeafd6"))
    )
    (comp (ref "TP1")
      (value "TPAD6R")
      (footprint "TP06R")
      (description "0.6mm round")
      (libsource (lib "ravindu tennakoon") (part "CMP-001-0001-4"))
    )
    (comp (ref "TP2")
      (value "TPAD6R")
      (footprint "TP06R")
      (description "0.6mm round")
      (libsource (lib "ravindu tennakoon") (part "CMP-001-0001-4"))
    )
    (comp (ref "TP3")
      (value "TPAD6R")
      (footprint "TP06R")
      (description "0.6mm round")
      (libsource (lib "ravindu tennakoon") (part "CMP-001-0001-4"))
    )
    (comp (ref "TP4")
      (value "TPAD6R")
      (footprint "TP06R")
      (description "0.6mm round")
      (libsource (lib "ravindu tennakoon") (part "CMP-001-0001-4"))
    )
    (comp (ref "TP5")
      (value "TPAD6R")
      (footprint "TP06R")
      (description "0.6mm round")
      (libsource (lib "ravindu tennakoon") (part "CMP-001-0001-4"))
    )
    (comp (ref "TP6")
      (value "TPAD6R")
      (footprint "TP06R")
      (description "0.6mm round")
      (libsource (lib "ravindu tennakoon") (part "CMP-001-0001-4"))
    )
    (comp (ref "TP8")
      (value "TPAD6R")
      (footprint "TP06R")
      (description "0.6mm round")
      (libsource (lib "ravindu tennakoon") (part "CMP-001-0001-4"))
    )
    (comp (ref "TP9")
      (value "TPAD6R")
      (footprint "TP06R")
      (description "0.6mm round")
      (libsource (lib "ravindu tennakoon") (part "CMP-001-0001-4"))
    )
    (comp (ref "TP10")
      (value "TPAD6R")
      (footprint "TP06R")
      (description "0.6mm round")
      (libsource (lib "ravindu tennakoon") (part "CMP-001-0001-4"))
    )
    (comp (ref "TP11")
      (value "TPAD6R")
      (footprint "TP06R")
      (description "0.6mm round")
      (libsource (lib "ravindu tennakoon") (part "CMP-001-0001-4"))
    )
    (comp (ref "U1")
      (value "STM32H743VIT6")
      (footprint "FP-LQFP100-1L-MFG")
      (description "IC MCU 32BIT 2MB FLASH 100LQFP")
      (fields
        (field (name "OCTOPART") "https://octopart.com/stm32h743vit6-stmicroelectronics-76372527")
        (field (name "MANUFACTURER") "STMicroelectronics")
      )
      (libsource (lib "") (part "01082ce2885d1d16a22823c45526fe6_1"))
    )
    (comp (ref "USB")
      (value "47346-0001")
      (footprint "FP-473460001-MFG")
      (description "Micro-USB B Receptacle with Flange, Bottom Mount, Surface Mount, Lead-Free")
      (libsource (lib "ravindu tennakoon") (part "53ae1f1d9b557310b43ca686e5bb76a"))
    )
    (comp (ref "Y1")
      (value "X322525MOB4SI")
      (footprint "SamacSys:X322525MOB4SI")
      (description "Crystal or Oscillator")
      (libsource (lib "*") (part "X322525MOB4SI"))
    )
  )
  (nets
    (net (code "1") (name "+3.3V") (class "Default")
      (node (ref "3.3V") (pin "1") (pinfunction "TP_1") (pintype "passive"))
      (node (ref "C10") (pin "2") (pinfunction "2_2") (pintype "passive"))
      (node (ref "C11") (pin "2") (pinfunction "2_2") (pintype "passive"))
      (node (ref "C5") (pin "1") (pinfunction "1_1") (pintype "passive"))
      (node (ref "C6") (pin "2") (pinfunction "2_2") (pintype "passive"))
      (node (ref "C7") (pin "2") (pinfunction "2_2") (pintype "passive"))
      (node (ref "C8") (pin "2") (pinfunction "2_2") (pintype "passive"))
      (node (ref "C9") (pin "2") (pinfunction "2_2") (pintype "passive"))
      (node (ref "D2") (pin "2") (pinfunction "A_2") (pintype "passive"))
      (node (ref "FB1") (pin "1") (pinfunction "1_1") (pintype "passive"))
      (node (ref "PWR") (pin "1") (pinfunction "1_1") (pintype "passive"))
      (node (ref "R10") (pin "1") (pinfunction "1_1") (pintype "passive"))
      (node (ref "R12") (pin "1") (pinfunction "1_1") (pintype "passive"))
      (node (ref "R14") (pin "1") (pinfunction "1_1") (pintype "passive"))
      (node (ref "R16") (pin "1") (pinfunction "1_1") (pintype "passive"))
      (node (ref "R18") (pin "1") (pinfunction "1_1") (pintype "passive"))
      (node (ref "R2") (pin "1") (pinfunction "1_1") (pintype "passive"))
      (node (ref "R25") (pin "1") (pinfunction "1_1") (pintype "passive"))
      (node (ref "R26") (pin "1") (pinfunction "1_1") (pintype "passive"))
      (node (ref "R29") (pin "1") (pinfunction "1_1") (pintype "passive"))
      (node (ref "R31") (pin "1") (pinfunction "1_1") (pintype "passive"))
      (node (ref "R33") (pin "2") (pinfunction "2_2") (pintype "passive"))
      (node (ref "R4") (pin "1") (pinfunction "1_1") (pintype "passive"))
      (node (ref "R6") (pin "1") (pinfunction "1_1") (pintype "passive"))
      (node (ref "R8") (pin "1") (pinfunction "1_1") (pintype "passive"))
      (node (ref "SW1") (pin "3") (pinfunction "3_3") (pintype "passive"))
      (node (ref "SWD") (pin "1") (pinfunction "1_1") (pintype "passive"))
      (node (ref "U1") (pin "100") (pinfunction "VDD_100") (pintype "power_in"))
      (node (ref "U1") (pin "11") (pinfunction "VDD_11") (pintype "power_in"))
      (node (ref "U1") (pin "27") (pinfunction "VDD_27") (pintype "power_in"))
      (node (ref "U1") (pin "50") (pinfunction "VDD_50") (pintype "power_in"))
      (node (ref "U1") (pin "6") (pinfunction "VBAT_6") (pintype "power_in"))
      (node (ref "U1") (pin "75") (pinfunction "VDD_75") (pintype "power_in"))
    )
    (net (code "2") (name "+5V") (class "Default")
      (node (ref "C14") (pin "1") (pinfunction "1_1") (pintype "passive"))
      (node (ref "R23") (pin "2") (pinfunction "2_2") (pintype "passive"))
      (node (ref "USB") (pin "1") (pinfunction "VBUS_1") (pintype "power_in"))
    )
    (net (code "3") (name "/B1DS") (class "Default")
      (node (ref "LED1") (pin "1") (pinfunction "1_1") (pintype "passive"))
      (node (ref "U1") (pin "80") (pinfunction "PC12_80") (pintype "bidirectional"))
    )
    (net (code "4") (name "/B1SHCP") (class "Default")
      (node (ref "LED1") (pin "2") (pinfunction "2_2") (pintype "passive"))
      (node (ref "U1") (pin "79") (pinfunction "PC11_79") (pintype "bidirectional"))
    )
    (net (code "5") (name "/B1STCP") (class "Default")
      (node (ref "LED1") (pin "3") (pinfunction "3_3") (pintype "passive"))
      (node (ref "U1") (pin "78") (pinfunction "PC10_78") (pintype "bidirectional"))
    )
    (net (code "6") (name "/B2DS") (class "Default")
      (node (ref "LED2") (pin "2") (pinfunction "2_2") (pintype "passive"))
      (node (ref "U1") (pin "5") (pinfunction "PE6_5") (pintype "bidirectional"))
    )
    (net (code "7") (name "/B2SHCP") (class "Default")
      (node (ref "LED2") (pin "3") (pinfunction "3_3") (pintype "passive"))
      (node (ref "U1") (pin "1") (pinfunction "PE2_1") (pintype "bidirectional"))
    )
    (net (code "8") (name "/B2STCP") (class "Default")
      (node (ref "LED2") (pin "1") (pinfunction "1_1") (pintype "passive"))
      (node (ref "TP8") (pin "1") (pinfunction "TP_1") (pintype "passive"))
      (node (ref "U1") (pin "2") (pinfunction "PE3_2") (pintype "bidirectional"))
    )
    (net (code "9") (name "/BOOT") (class "Default")
      (node (ref "C2") (pin "2") (pinfunction "2_2") (pintype "passive"))
      (node (ref "R34") (pin "2") (pinfunction "2_2") (pintype "passive"))
      (node (ref "SW1") (pin "2") (pinfunction "2_2") (pintype "passive"))
      (node (ref "TP2") (pin "1") (pinfunction "TP_1") (pintype "passive"))
      (node (ref "U1") (pin "94") (pinfunction "BOOT0_94") (pintype "input"))
    )
    (net (code "10") (name "/D1_CS") (class "Default")
      (node (ref "LCD1_C") (pin "2") (pinfunction "2_2") (pintype "passive"))
      (node (ref "U1") (pin "36") (pinfunction "PB2_36") (pintype "bidirectional"))
    )
    (net (code "11") (name "/D1_D0") (class "Default")
      (node (ref "LCD1_D") (pin "8") (pinfunction "8_8") (pintype "passive"))
      (node (ref "U1") (pin "38") (pinfunction "PE8_38") (pintype "bidirectional"))
    )
    (net (code "12") (name "/D1_D1") (class "Default")
      (node (ref "LCD1_D") (pin "7") (pinfunction "7_7") (pintype "passive"))
      (node (ref "U1") (pin "39") (pinfunction "PE9_39") (pintype "bidirectional"))
    )
    (net (code "13") (name "/D1_D2") (class "Default")
      (node (ref "LCD1_D") (pin "6") (pinfunction "6_6") (pintype "passive"))
      (node (ref "U1") (pin "40") (pinfunction "PE10_40") (pintype "bidirectional"))
    )
    (net (code "14") (name "/D1_D3") (class "Default")
      (node (ref "LCD1_D") (pin "5") (pinfunction "5_5") (pintype "passive"))
      (node (ref "U1") (pin "41") (pinfunction "PE11_41") (pintype "bidirectional"))
    )
    (net (code "15") (name "/D1_D4") (class "Default")
      (node (ref "LCD1_D") (pin "4") (pinfunction "4_4") (pintype "passive"))
      (node (ref "U1") (pin "42") (pinfunction "PE12_42") (pintype "bidirectional"))
    )
    (net (code "16") (name "/D1_D5") (class "Default")
      (node (ref "LCD1_D") (pin "3") (pinfunction "3_3") (pintype "passive"))
      (node (ref "U1") (pin "43") (pinfunction "PE13_43") (pintype "bidirectional"))
    )
    (net (code "17") (name "/D1_D6") (class "Default")
      (node (ref "LCD1_D") (pin "2") (pinfunction "2_2") (pintype "passive"))
      (node (ref "U1") (pin "44") (pinfunction "PE14_44") (pintype "bidirectional"))
    )
    (net (code "18") (name "/D1_D7") (class "Default")
      (node (ref "LCD1_D") (pin "1") (pinfunction "1_1") (pintype "passive"))
      (node (ref "U1") (pin "45") (pinfunction "PE15_45") (pintype "bidirectional"))
    )
    (net (code "19") (name "/D1_RD") (class "Default")
      (node (ref "LCD1_C") (pin "5") (pinfunction "5_5") (pintype "passive"))
      (node (ref "U1") (pin "33") (pinfunction "PC5_33") (pintype "bidirectional"))
    )
    (net (code "20") (name "/D1_RS") (class "Default")
      (node (ref "LCD1_C") (pin "3") (pinfunction "3_3") (pintype "passive"))
      (node (ref "U1") (pin "35") (pinfunction "PB1_35") (pintype "bidirectional"))
    )
    (net (code "21") (name "/D1_RST") (class "Default")
      (node (ref "LCD1_C") (pin "1") (pinfunction "1_1") (pintype "passive"))
      (node (ref "TP4") (pin "1") (pinfunction "TP_1") (pintype "passive"))
      (node (ref "U1") (pin "37") (pinfunction "PE7_37") (pintype "bidirectional"))
    )
    (net (code "22") (name "/D1_WR") (class "Default")
      (node (ref "LCD1_C") (pin "4") (pinfunction "4_4") (pintype "passive"))
      (node (ref "U1") (pin "34") (pinfunction "PB0_34") (pintype "bidirectional"))
    )
    (net (code "23") (name "/D2_CS") (class "Default")
      (node (ref "LCD2_C") (pin "2") (pinfunction "2_2") (pintype "passive"))
      (node (ref "U1") (pin "66") (pinfunction "PC9_66") (pintype "bidirectional"))
    )
    (net (code "24") (name "/D2_D0") (class "Default")
      (node (ref "LCD2_D") (pin "8") (pinfunction "8_8") (pintype "passive"))
      (node (ref "U1") (pin "55") (pinfunction "PD8_55") (pintype "bidirectional"))
    )
    (net (code "25") (name "/D2_D1") (class "Default")
      (node (ref "LCD2_D") (pin "7") (pinfunction "7_7") (pintype "passive"))
      (node (ref "U1") (pin "56") (pinfunction "PD9_56") (pintype "bidirectional"))
    )
    (net (code "26") (name "/D2_D2") (class "Default")
      (node (ref "LCD2_D") (pin "6") (pinfunction "6_6") (pintype "passive"))
      (node (ref "U1") (pin "57") (pinfunction "PD10_57") (pintype "bidirectional"))
    )
    (net (code "27") (name "/D2_D3") (class "Default")
      (node (ref "LCD2_D") (pin "5") (pinfunction "5_5") (pintype "passive"))
      (node (ref "U1") (pin "58") (pinfunction "PD11_58") (pintype "bidirectional"))
    )
    (net (code "28") (name "/D2_D4") (class "Default")
      (node (ref "LCD2_D") (pin "4") (pinfunction "4_4") (pintype "passive"))
      (node (ref "U1") (pin "59") (pinfunction "PD12_59") (pintype "bidirectional"))
    )
    (net (code "29") (name "/D2_D5") (class "Default")
      (node (ref "LCD2_D") (pin "3") (pinfunction "3_3") (pintype "passive"))
      (node (ref "U1") (pin "60") (pinfunction "PD13_60") (pintype "bidirectional"))
    )
    (net (code "30") (name "/D2_D6") (class "Default")
      (node (ref "LCD2_D") (pin "2") (pinfunction "2_2") (pintype "passive"))
      (node (ref "U1") (pin "61") (pinfunction "PD14_61") (pintype "bidirectional"))
    )
    (net (code "31") (name "/D2_D7") (class "Default")
      (node (ref "LCD2_D") (pin "1") (pinfunction "1_1") (pintype "passive"))
      (node (ref "U1") (pin "62") (pinfunction "PD15_62") (pintype "bidirectional"))
    )
    (net (code "32") (name "/D2_RD") (class "Default")
      (node (ref "LCD2_C") (pin "5") (pinfunction "5_5") (pintype "passive"))
      (node (ref "TP5") (pin "1") (pinfunction "TP_1") (pintype "passive"))
      (node (ref "U1") (pin "63") (pinfunction "PC6_63") (pintype "bidirectional"))
    )
    (net (code "33") (name "/D2_RS") (class "Default")
      (node (ref "LCD2_C") (pin "3") (pinfunction "3_3") (pintype "passive"))
      (node (ref "U1") (pin "65") (pinfunction "PC8_65") (pintype "bidirectional"))
    )
    (net (code "34") (name "/D2_RST") (class "Default")
      (node (ref "LCD2_C") (pin "1") (pinfunction "1_1") (pintype "passive"))
      (node (ref "U1") (pin "67") (pinfunction "PA8_67") (pintype "bidirectional"))
    )
    (net (code "35") (name "/D2_WR") (class "Default")
      (node (ref "LCD2_C") (pin "4") (pinfunction "4_4") (pintype "passive"))
      (node (ref "U1") (pin "64") (pinfunction "PC7_64") (pintype "bidirectional"))
    )
    (net (code "36") (name "/DOWN") (class "Default")
      (node (ref "C27") (pin "1") (pinfunction "1_1") (pintype "passive"))
      (node (ref "R15") (pin "1") (pinfunction "1_1") (pintype "passive"))
      (node (ref "U1") (pin "92") (pinfunction "PB6_92") (pintype "bidirectional"))
    )
    (net (code "37") (name "/DOWN_I") (class "Default")
      (node (ref "KEY_CON") (pin "4") (pinfunction "4_4") (pintype "passive"))
      (node (ref "R14") (pin "2") (pinfunction "2_2") (pintype "passive"))
      (node (ref "R15") (pin "2") (pinfunction "2_2") (pintype "passive"))
    )
    (net (code "38") (name "/K_C1") (class "Default")
      (node (ref "C20") (pin "1") (pinfunction "1_1") (pintype "passive"))
      (node (ref "R27") (pin "1") (pinfunction "1_1") (pintype "passive"))
      (node (ref "U1") (pin "84") (pinfunction "PD3_84") (pintype "bidirectional"))
    )
    (net (code "39") (name "/K_C1_I") (class "Default")
      (node (ref "KEY_C") (pin "1") (pinfunction "1_1") (pintype "passive"))
      (node (ref "R25") (pin "2") (pinfunction "2_2") (pintype "passive"))
      (node (ref "R27") (pin "2") (pinfunction "2_2") (pintype "passive"))
    )
    (net (code "40") (name "/K_C2") (class "Default")
      (node (ref "C29") (pin "1") (pinfunction "1_1") (pintype "passive"))
      (node (ref "R28") (pin "1") (pinfunction "1_1") (pintype "passive"))
      (node (ref "U1") (pin "83") (pinfunction "PD2_83") (pintype "bidirectional"))
    )
    (net (code "41") (name "/K_C2_I") (class "Default")
      (node (ref "KEY_C") (pin "2") (pinfunction "2_2") (pintype "passive"))
      (node (ref "R26") (pin "2") (pinfunction "2_2") (pintype "passive"))
      (node (ref "R28") (pin "2") (pinfunction "2_2") (pintype "passive"))
    )
    (net (code "42") (name "/K_C3") (class "Default")
      (node (ref "C31") (pin "1") (pinfunction "1_1") (pintype "passive"))
      (node (ref "R30") (pin "1") (pinfunction "1_1") (pintype "passive"))
      (node (ref "U1") (pin "82") (pinfunction "PD1_82") (pintype "bidirectional"))
    )
    (net (code "43") (name "/K_C3_I") (class "Default")
      (node (ref "KEY_C") (pin "3") (pinfunction "3_3") (pintype "passive"))
      (node (ref "R29") (pin "2") (pinfunction "2_2") (pintype "passive"))
      (node (ref "R30") (pin "2") (pinfunction "2_2") (pintype "passive"))
    )
    (net (code "44") (name "/K_C4") (class "Default")
      (node (ref "C32") (pin "1") (pinfunction "1_1") (pintype "passive"))
      (node (ref "R32") (pin "1") (pinfunction "1_1") (pintype "passive"))
      (node (ref "U1") (pin "81") (pinfunction "PD0_81") (pintype "bidirectional"))
    )
    (net (code "45") (name "/K_C4_I") (class "Default")
      (node (ref "KEY_C") (pin "4") (pinfunction "4_4") (pintype "passive"))
      (node (ref "R31") (pin "2") (pinfunction "2_2") (pintype "passive"))
      (node (ref "R32") (pin "2") (pinfunction "2_2") (pintype "passive"))
    )
    (net (code "46") (name "/K_R1") (class "Default")
      (node (ref "C21") (pin "1") (pinfunction "1_1") (pintype "passive"))
      (node (ref "R3") (pin "1") (pinfunction "1_1") (pintype "passive"))
      (node (ref "U1") (pin "88") (pinfunction "PD7_88") (pintype "bidirectional"))
    )
    (net (code "47") (name "/K_R1_I") (class "Default")
      (node (ref "KEY_R") (pin "1") (pinfunction "1_1") (pintype "passive"))
      (node (ref "R2") (pin "2") (pinfunction "2_2") (pintype "passive"))
      (node (ref "R3") (pin "2") (pinfunction "2_2") (pintype "passive"))
      (node (ref "TP3") (pin "1") (pinfunction "TP_1") (pintype "passive"))
    )
    (net (code "48") (name "/K_R2") (class "Default")
      (node (ref "C22") (pin "1") (pinfunction "1_1") (pintype "passive"))
      (node (ref "R5") (pin "1") (pinfunction "1_1") (pintype "passive"))
      (node (ref "U1") (pin "87") (pinfunction "PD6_87") (pintype "bidirectional"))
    )
    (net (code "49") (name "/K_R2_I") (class "Default")
      (node (ref "KEY_R") (pin "2") (pinfunction "2_2") (pintype "passive"))
      (node (ref "R4") (pin "2") (pinfunction "2_2") (pintype "passive"))
      (node (ref "R5") (pin "2") (pinfunction "2_2") (pintype "passive"))
    )
    (net (code "50") (name "/K_R3") (class "Default")
      (node (ref "C23") (pin "1") (pinfunction "1_1") (pintype "passive"))
      (node (ref "R7") (pin "1") (pinfunction "1_1") (pintype "passive"))
      (node (ref "U1") (pin "86") (pinfunction "PD5_86") (pintype "bidirectional"))
    )
    (net (code "51") (name "/K_R3_I") (class "Default")
      (node (ref "KEY_R") (pin "3") (pinfunction "3_3") (pintype "passive"))
      (node (ref "R6") (pin "2") (pinfunction "2_2") (pintype "passive"))
      (node (ref "R7") (pin "2") (pinfunction "2_2") (pintype "passive"))
    )
    (net (code "52") (name "/K_R4") (class "Default")
      (node (ref "C24") (pin "1") (pinfunction "1_1") (pintype "passive"))
      (node (ref "R9") (pin "1") (pinfunction "1_1") (pintype "passive"))
      (node (ref "U1") (pin "85") (pinfunction "PD4_85") (pintype "bidirectional"))
    )
    (net (code "53") (name "/K_R4_I") (class "Default")
      (node (ref "KEY_R") (pin "4") (pinfunction "4_4") (pintype "passive"))
      (node (ref "R8") (pin "2") (pinfunction "2_2") (pintype "passive"))
      (node (ref "R9") (pin "2") (pinfunction "2_2") (pintype "passive"))
    )
    (net (code "54") (name "/LEFT") (class "Default")
      (node (ref "C28") (pin "1") (pinfunction "1_1") (pintype "passive"))
      (node (ref "R17") (pin "1") (pinfunction "1_1") (pintype "passive"))
      (node (ref "U1") (pin "93") (pinfunction "PB7_93") (pintype "bidirectional"))
    )
    (net (code "55") (name "/LEFT_I") (class "Default")
      (node (ref "KEY_CON") (pin "3") (pinfunction "3_3") (pintype "passive"))
      (node (ref "R16") (pin "2") (pinfunction "2_2") (pintype "passive"))
      (node (ref "R17") (pin "2") (pinfunction "2_2") (pintype "passive"))
    )
    (net (code "56") (name "/NRST") (class "Default")
      (node (ref "C1") (pin "2") (pinfunction "2_2") (pintype "passive"))
      (node (ref "R33") (pin "1") (pinfunction "1_1") (pintype "passive"))
      (node (ref "SW1") (pin "1") (pinfunction "1_1") (pintype "passive"))
      (node (ref "SWD") (pin "5") (pinfunction "5_5") (pintype "passive"))
      (node (ref "TP1") (pin "1") (pinfunction "TP_1") (pintype "passive"))
      (node (ref "U1") (pin "14") (pinfunction "~{RST}_14") (pintype "input"))
    )
    (net (code "57") (name "/OK") (class "Default")
      (node (ref "C25") (pin "1") (pinfunction "1_1") (pintype "passive"))
      (node (ref "R11") (pin "1") (pinfunction "1_1") (pintype "passive"))
      (node (ref "U1") (pin "96") (pinfunction "PB9_96") (pintype "bidirectional"))
    )
    (net (code "58") (name "/OK_I") (class "Default")
      (node (ref "KEY_CON") (pin "1") (pinfunction "1_1") (pintype "passive"))
      (node (ref "R10") (pin "2") (pinfunction "2_2") (pintype "passive"))
      (node (ref "R11") (pin "2") (pinfunction "2_2") (pintype "passive"))
    )
    (net (code "59") (name "/P1") (class "Default")
      (node (ref "C18") (pin "1") (pinfunction "1_1") (pintype "passive"))
      (node (ref "R21") (pin "1") (pinfunction "1_1") (pintype "passive"))
      (node (ref "TP11") (pin "1") (pinfunction "TP_1") (pintype "passive"))
      (node (ref "U1") (pin "25") (pinfunction "PA3_25") (pintype "bidirectional"))
    )
    (net (code "60") (name "/RIGHT") (class "Default")
      (node (ref "C30") (pin "1") (pinfunction "1_1") (pintype "passive"))
      (node (ref "R19") (pin "1") (pinfunction "1_1") (pintype "passive"))
      (node (ref "U1") (pin "95") (pinfunction "PB8_95") (pintype "bidirectional"))
    )
    (net (code "61") (name "/RIGHT_I") (class "Default")
      (node (ref "KEY_CON") (pin "2") (pinfunction "2_2") (pintype "passive"))
      (node (ref "R18") (pin "2") (pinfunction "2_2") (pintype "passive"))
      (node (ref "R19") (pin "2") (pinfunction "2_2") (pintype "passive"))
    )
    (net (code "62") (name "/S1DS") (class "Default")
      (node (ref "LED3") (pin "1") (pinfunction "1_1") (pintype "passive"))
      (node (ref "U1") (pin "31") (pinfunction "PA7_31") (pintype "bidirectional"))
    )
    (net (code "63") (name "/S2SHCP") (class "Default")
      (node (ref "LED3") (pin "3") (pinfunction "3_3") (pintype "passive"))
      (node (ref "TP9") (pin "1") (pinfunction "TP_1") (pintype "passive"))
      (node (ref "U1") (pin "29") (pinfunction "PA5_29") (pintype "bidirectional"))
    )
    (net (code "64") (name "/S2STCP") (class "Default")
      (node (ref "LED3") (pin "2") (pinfunction "2_2") (pintype "passive"))
      (node (ref "U1") (pin "30") (pinfunction "PA6_30") (pintype "bidirectional"))
    )
    (net (code "65") (name "/SWCLK") (class "Default")
      (node (ref "SWD") (pin "3") (pinfunction "3_3") (pintype "passive"))
      (node (ref "U1") (pin "76") (pinfunction "PA14_76") (pintype "bidirectional"))
    )
    (net (code "66") (name "/SWDIO") (class "Default")
      (node (ref "SWD") (pin "2") (pinfunction "2_2") (pintype "passive"))
      (node (ref "TP10") (pin "1") (pinfunction "TP_1") (pintype "passive"))
      (node (ref "U1") (pin "72") (pinfunction "PA13_72") (pintype "bidirectional"))
    )
    (net (code "67") (name "/SWO") (class "Default")
      (node (ref "SWD") (pin "4") (pinfunction "4_4") (pintype "passive"))
      (node (ref "U1") (pin "89") (pinfunction "PB3_89") (pintype "bidirectional"))
    )
    (net (code "68") (name "/Test") (class "Default")
      (node (ref "D3") (pin "2") (pinfunction "A_2") (pintype "passive"))
      (node (ref "U1") (pin "51") (pinfunction "PB12_51") (pintype "bidirectional"))
    )
    (net (code "69") (name "/UP") (class "Default")
      (node (ref "C26") (pin "1") (pinfunction "1_1") (pintype "passive"))
      (node (ref "R13") (pin "1") (pinfunction "1_1") (pintype "passive"))
      (node (ref "U1") (pin "91") (pinfunction "PB5_91") (pintype "bidirectional"))
    )
    (net (code "70") (name "/UP_I") (class "Default")
      (node (ref "KEY_CON") (pin "5") (pinfunction "5_5") (pintype "passive"))
      (node (ref "R12") (pin "2") (pinfunction "2_2") (pintype "passive"))
      (node (ref "R13") (pin "2") (pinfunction "2_2") (pintype "passive"))
      (node (ref "TP6") (pin "1") (pinfunction "TP_1") (pintype "passive"))
    )
    (net (code "71") (name "/USBD_N") (class "Default")
      (node (ref "U1") (pin "70") (pinfunction "PA11_70") (pintype "bidirectional"))
      (node (ref "USB") (pin "2") (pinfunction "D-_2") (pintype "bidirectional"))
    )
    (net (code "72") (name "/USBD_P") (class "Default")
      (node (ref "U1") (pin "71") (pinfunction "PA12_71") (pintype "bidirectional"))
      (node (ref "USB") (pin "3") (pinfunction "D+_3") (pintype "bidirectional"))
    )
    (net (code "73") (name "/VBUS_Sense") (class "Default")
      (node (ref "R23") (pin "1") (pinfunction "1_1") (pintype "passive"))
      (node (ref "R24") (pin "2") (pinfunction "2_2") (pintype "passive"))
      (node (ref "U1") (pin "68") (pinfunction "PA9_68") (pintype "bidirectional"))
    )
    (net (code "74") (name "GND") (class "Default")
      (node (ref "C1") (pin "1") (pinfunction "1_1") (pintype "passive"))
      (node (ref "C10") (pin "1") (pinfunction "1_1") (pintype "passive"))
      (node (ref "C11") (pin "1") (pinfunction "1_1") (pintype "passive"))
      (node (ref "C12") (pin "2") (pinfunction "2_2") (pintype "passive"))
      (node (ref "C13") (pin "2") (pinfunction "2_2") (pintype "passive"))
      (node (ref "C14") (pin "2") (pinfunction "2_2") (pintype "passive"))
      (node (ref "C15") (pin "1") (pinfunction "1_1") (pintype "passive"))
      (node (ref "C16") (pin "2") (pinfunction "2_2") (pintype "passive"))
      (node (ref "C17") (pin "1") (pinfunction "1_1") (pintype "passive"))
      (node (ref "C18") (pin "2") (pinfunction "2_2") (pintype "passive"))
      (node (ref "C19") (pin "2") (pinfunction "2_2") (pintype "passive"))
      (node (ref "C2") (pin "1") (pinfunction "1_1") (pintype "passive"))
      (node (ref "C20") (pin "2") (pinfunction "2_2") (pintype "passive"))
      (node (ref "C21") (pin "2") (pinfunction "2_2") (pintype "passive"))
      (node (ref "C22") (pin "2") (pinfunction "2_2") (pintype "passive"))
      (node (ref "C23") (pin "2") (pinfunction "2_2") (pintype "passive"))
      (node (ref "C24") (pin "2") (pinfunction "2_2") (pintype "passive"))
      (node (ref "C25") (pin "2") (pinfunction "2_2") (pintype "passive"))
      (node (ref "C26") (pin "2") (pinfunction "2_2") (pintype "passive"))
      (node (ref "C27") (pin "2") (pinfunction "2_2") (pintype "passive"))
      (node (ref "C28") (pin "2") (pinfunction "2_2") (pintype "passive"))
      (node (ref "C29") (pin "2") (pinfunction "2_2") (pintype "passive"))
      (node (ref "C3") (pin "2") (pinfunction "2_2") (pintype "passive"))
      (node (ref "C30") (pin "2") (pinfunction "2_2") (pintype "passive"))
      (node (ref "C31") (pin "2") (pinfunction "2_2") (pintype "passive"))
      (node (ref "C32") (pin "2") (pinfunction "2_2") (pintype "passive"))
      (node (ref "C4") (pin "1") (pinfunction "1_1") (pintype "passive"))
      (node (ref "C5") (pin "2") (pinfunction "2_2") (pintype "passive"))
      (node (ref "C6") (pin "1") (pinfunction "1_1") (pintype "passive"))
      (node (ref "C7") (pin "1") (pinfunction "1_1") (pintype "passive"))
      (node (ref "C8") (pin "1") (pinfunction "1_1") (pintype "passive"))
      (node (ref "C9") (pin "1") (pinfunction "1_1") (pintype "passive"))
      (node (ref "GND") (pin "1") (pinfunction "TP_1") (pintype "passive"))
      (node (ref "PWR") (pin "2") (pinfunction "2_2") (pintype "passive"))
      (node (ref "R20") (pin "1") (pinfunction "1_1") (pintype "passive"))
      (node (ref "R22") (pin "1") (pinfunction "1_1") (pintype "passive"))
      (node (ref "R24") (pin "1") (pinfunction "1_1") (pintype "passive"))
      (node (ref "R34") (pin "1") (pinfunction "1_1") (pintype "passive"))
      (node (ref "SW1") (pin "4") (pinfunction "4_4") (pintype "passive"))
      (node (ref "SWD") (pin "6") (pinfunction "6_6") (pintype "passive"))
      (node (ref "U1") (pin "10") (pinfunction "VSS_10") (pintype "power_in"))
      (node (ref "U1") (pin "19") (pinfunction "VSSA_19") (pintype "power_in"))
      (node (ref "U1") (pin "26") (pinfunction "VSS_26") (pintype "power_in"))
      (node (ref "U1") (pin "49") (pinfunction "VSS_49") (pintype "power_in"))
      (node (ref "U1") (pin "74") (pinfunction "VSS_74") (pintype "power_in"))
      (node (ref "U1") (pin "99") (pinfunction "VSS_99") (pintype "power_in"))
      (node (ref "USB") (pin "5") (pinfunction "GND_5") (pintype "power_in"))
      (node (ref "Y1") (pin "2") (pinfunction "GND_1_2") (pintype "passive"))
      (node (ref "Y1") (pin "4") (pinfunction "GND_2_4") (pintype "passive"))
    )
    (net (code "75") (name "Net-(C12-Pad1)") (class "Default")
      (node (ref "C12") (pin "1") (pinfunction "1_1") (pintype "passive"))
      (node (ref "U1") (pin "73") (pinfunction "VCAP_73") (pintype "passive"))
    )
    (net (code "76") (name "Net-(C13-Pad1)") (class "Default")
      (node (ref "C13") (pin "1") (pinfunction "1_1") (pintype "passive"))
      (node (ref "U1") (pin "48") (pinfunction "VCAP_48") (pintype "passive"))
    )
    (net (code "77") (name "Net-(D2-C)") (class "Default")
      (node (ref "D2") (pin "1") (pinfunction "C_1") (pintype "passive"))
      (node (ref "R20") (pin "2") (pinfunction "2_2") (pintype "passive"))
    )
    (net (code "78") (name "Net-(D3-C)") (class "Default")
      (node (ref "D3") (pin "1") (pinfunction "C_1") (pintype "passive"))
      (node (ref "R22") (pin "2") (pinfunction "2_2") (pintype "passive"))
    )
    (net (code "79") (name "Net-(POT-Pad1)") (class "Default")
      (node (ref "POT") (pin "1") (pinfunction "1_1") (pintype "passive"))
      (node (ref "R21") (pin "2") (pinfunction "2_2") (pintype "passive"))
    )
    (net (code "80") (name "Net-(U1B-PH0-OSC_IN)") (class "Default")
      (node (ref "C3") (pin "1") (pinfunction "1_1") (pintype "passive"))
      (node (ref "U1") (pin "12") (pinfunction "PH0-OSC_IN_12") (pintype "bidirectional"))
      (node (ref "Y1") (pin "3") (pinfunction "CRYSTAL__2_3") (pintype "passive"))
    )
    (net (code "81") (name "Net-(U1B-PH1-OSC_OUT)") (class "Default")
      (node (ref "C4") (pin "2") (pinfunction "2_2") (pintype "passive"))
      (node (ref "U1") (pin "13") (pinfunction "PH1-OSC_OUT_13") (pintype "bidirectional"))
      (node (ref "Y1") (pin "1") (pinfunction "CRYSTAL__1_1") (pintype "passive"))
    )
    (net (code "82") (name "Net-(U1C-VDDA)") (class "Default")
      (node (ref "C17") (pin "2") (pinfunction "2_2") (pintype "passive"))
      (node (ref "C19") (pin "1") (pinfunction "1_1") (pintype "passive"))
      (node (ref "FB1") (pin "2") (pinfunction "2_2") (pintype "passive"))
      (node (ref "R1") (pin "1") (pinfunction "1_1") (pintype "passive"))
      (node (ref "U1") (pin "21") (pinfunction "VDDA_21") (pintype "power_in"))
    )
    (net (code "83") (name "Net-(U1C-VREF+)") (class "Default")
      (node (ref "C15") (pin "2") (pinfunction "2_2") (pintype "passive"))
      (node (ref "C16") (pin "1") (pinfunction "1_1") (pintype "passive"))
      (node (ref "R1") (pin "2") (pinfunction "2_2") (pintype "passive"))
      (node (ref "U1") (pin "20") (pinfunction "VREF+_20") (pintype "power_in"))
    )
    (net (code "84") (name "unconnected-(MH1-H1-Pad1)") (class "Default")
      (node (ref "MH1") (pin "1") (pinfunction "H1_1") (pintype "passive"))
    )
    (net (code "85") (name "unconnected-(MH2-H1-Pad1)") (class "Default")
      (node (ref "MH2") (pin "1") (pinfunction "H1_1") (pintype "passive"))
    )
    (net (code "86") (name "unconnected-(MH3-H1-Pad1)") (class "Default")
      (node (ref "MH3") (pin "1") (pinfunction "H1_1") (pintype "passive"))
    )
    (net (code "87") (name "unconnected-(MH4-H1-Pad1)") (class "Default")
      (node (ref "MH4") (pin "1") (pinfunction "H1_1") (pintype "passive"))
    )
    (net (code "88") (name "unconnected-(POT-Pad2)") (class "Default")
      (node (ref "POT") (pin "2") (pinfunction "2_2") (pintype "passive+no_connect"))
    )
    (net (code "89") (name "unconnected-(U1A-PA0-Pad22)") (class "Default")
      (node (ref "U1") (pin "22") (pinfunction "PA0_22") (pintype "bidirectional+no_connect"))
    )
    (net (code "90") (name "unconnected-(U1A-PA1-Pad23)") (class "Default")
      (node (ref "U1") (pin "23") (pinfunction "PA1_23") (pintype "bidirectional+no_connect"))
    )
    (net (code "91") (name "unconnected-(U1A-PA2-Pad24)") (class "Default")
      (node (ref "U1") (pin "24") (pinfunction "PA2_24") (pintype "bidirectional+no_connect"))
    )
    (net (code "92") (name "unconnected-(U1A-PA4-Pad28)") (class "Default")
      (node (ref "U1") (pin "28") (pinfunction "PA4_28") (pintype "bidirectional+no_connect"))
    )
    (net (code "93") (name "unconnected-(U1A-PA10-Pad69)") (class "Default")
      (node (ref "U1") (pin "69") (pinfunction "PA10_69") (pintype "bidirectional+no_connect"))
    )
    (net (code "94") (name "unconnected-(U1A-PA15-Pad77)") (class "Default")
      (node (ref "U1") (pin "77") (pinfunction "PA15_77") (pintype "bidirectional+no_connect"))
    )
    (net (code "95") (name "unconnected-(U1A-PB4-Pad90)") (class "Default")
      (node (ref "U1") (pin "90") (pinfunction "PB4_90") (pintype "bidirectional+no_connect"))
    )
    (net (code "96") (name "unconnected-(U1A-PB10-Pad46)") (class "Default")
      (node (ref "U1") (pin "46") (pinfunction "PB10_46") (pintype "bidirectional+no_connect"))
    )
    (net (code "97") (name "unconnected-(U1A-PB11-Pad47)") (class "Default")
      (node (ref "U1") (pin "47") (pinfunction "PB11_47") (pintype "bidirectional+no_connect"))
    )
    (net (code "98") (name "unconnected-(U1A-PB13-Pad52)") (class "Default")
      (node (ref "U1") (pin "52") (pinfunction "PB13_52") (pintype "bidirectional+no_connect"))
    )
    (net (code "99") (name "unconnected-(U1A-PB14-Pad53)") (class "Default")
      (node (ref "U1") (pin "53") (pinfunction "PB14_53") (pintype "bidirectional+no_connect"))
    )
    (net (code "100") (name "unconnected-(U1A-PB15-Pad54)") (class "Default")
      (node (ref "U1") (pin "54") (pinfunction "PB15_54") (pintype "bidirectional+no_connect"))
    )
    (net (code "101") (name "unconnected-(U1A-PC0-Pad15)") (class "Default")
      (node (ref "U1") (pin "15") (pinfunction "PC0_15") (pintype "bidirectional+no_connect"))
    )
    (net (code "102") (name "unconnected-(U1A-PC1-Pad16)") (class "Default")
      (node (ref "U1") (pin "16") (pinfunction "PC1_16") (pintype "bidirectional+no_connect"))
    )
    (net (code "103") (name "unconnected-(U1A-PC2_C-Pad17)") (class "Default")
      (node (ref "U1") (pin "17") (pinfunction "PC2_C_17") (pintype "bidirectional+no_connect"))
    )
    (net (code "104") (name "unconnected-(U1A-PC3_C-Pad18)") (class "Default")
      (node (ref "U1") (pin "18") (pinfunction "PC3_C_18") (pintype "bidirectional+no_connect"))
    )
    (net (code "105") (name "unconnected-(U1A-PC4-Pad32)") (class "Default")
      (node (ref "U1") (pin "32") (pinfunction "PC4_32") (pintype "bidirectional+no_connect"))
    )
    (net (code "106") (name "unconnected-(U1A-PC13-Pad7)") (class "Default")
      (node (ref "U1") (pin "7") (pinfunction "PC13_7") (pintype "bidirectional+no_connect"))
    )
    (net (code "107") (name "unconnected-(U1A-PC14-OSC32_IN-Pad8)") (class "Default")
      (node (ref "U1") (pin "8") (pinfunction "PC14-OSC32_IN_8") (pintype "bidirectional+no_connect"))
    )
    (net (code "108") (name "unconnected-(U1A-PC15-OSC32_OUT-Pad9)") (class "Default")
      (node (ref "U1") (pin "9") (pinfunction "PC15-OSC32_OUT_9") (pintype "bidirectional+no_connect"))
    )
    (net (code "109") (name "unconnected-(U1B-PE0-Pad97)") (class "Default")
      (node (ref "U1") (pin "97") (pinfunction "PE0_97") (pintype "bidirectional+no_connect"))
    )
    (net (code "110") (name "unconnected-(U1B-PE1-Pad98)") (class "Default")
      (node (ref "U1") (pin "98") (pinfunction "PE1_98") (pintype "bidirectional+no_connect"))
    )
    (net (code "111") (name "unconnected-(U1B-PE4-Pad3)") (class "Default")
      (node (ref "U1") (pin "3") (pinfunction "PE4_3") (pintype "bidirectional+no_connect"))
    )
    (net (code "112") (name "unconnected-(U1B-PE5-Pad4)") (class "Default")
      (node (ref "U1") (pin "4") (pinfunction "PE5_4") (pintype "bidirectional+no_connect"))
    )
    (net (code "113") (name "unconnected-(USB-ID-Pad4)") (class "Default")
      (node (ref "USB") (pin "4") (pinfunction "ID_4") (pintype "passive+no_connect"))
    )
    (net (code "114") (name "unconnected-(USB-MNT_1-Pad6)") (class "Default")
      (node (ref "USB") (pin "6") (pinfunction "MNT_1_6") (pintype "passive+no_connect"))
    )
    (net (code "115") (name "unconnected-(USB-MNT_2-Pad7)") (class "Default")
      (node (ref "USB") (pin "7") (pinfunction "MNT_2_7") (pintype "passive+no_connect"))
    )
    (net (code "116") (name "unconnected-(USB-MNT_3-Pad8)") (class "Default")
      (node (ref "USB") (pin "8") (pinfunction "MNT_3_8") (pintype "passive+no_connect"))
    )
    (net (code "117") (name "unconnected-(USB-MNT_4-Pad9)") (class "Default")
      (node (ref "USB") (pin "9") (pinfunction "MNT_4_9") (pintype "passive+no_connect"))
    )
    (net (code "118") (name "unconnected-(USB-MNT_5-Pad10)") (class "Default")
      (node (ref "USB") (pin "10") (pinfunction "MNT_5_10") (pintype "passive+no_connect"))
    )
    (net (code "119") (name "unconnected-(USB-MNT_6-Pad11)") (class "Default")
      (node (ref "USB") (pin "11") (pinfunction "MNT_6_11") (pintype "passive+no_connect"))
    )
  )
)
